# 3V-16V_to_5V3A_DC-DC_Converter.net
KiCad netlist of a schematic drawn in Altium Designer
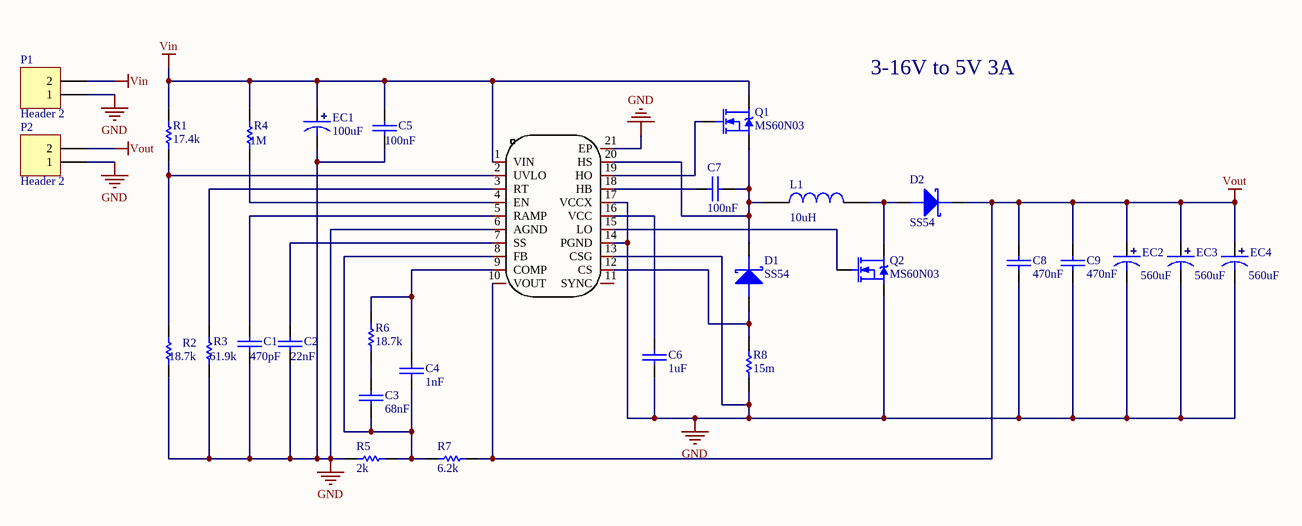
[diagram p0: 3V-16V to 5V3A DC-DC Converter.SchDoc]

(export (version "E")
  (design (tool "Eeschema 10.0.6"))
  (components
    (comp (ref "C1")
      (value "470pF")
      (footprint "0402C")
      (description "无极性电容")
      (libsource (lib "电容") (part "CAP"))
    )
    (comp (ref "C2")
      (value "22nF")
      (footprint "0402C")
      (description "无极性电容")
      (libsource (lib "电容") (part "CAP"))
    )
    (comp (ref "C3")
      (value "68nF")
      (footprint "0402C")
      (description "无极性电容")
      (libsource (lib "电容") (part "CAP"))
    )
    (comp (ref "C4")
      (value "1nF")
      (footprint "0402C")
      (description "无极性电容")
      (libsource (lib "电容") (part "CAP"))
    )
    (comp (ref "C5")
      (value "100nF")
      (footprint "0402C")
      (description "无极性电容")
      (libsource (lib "电容") (part "CAP"))
    )
    (comp (ref "C6")
      (value "1uF")
      (footprint "0402C")
      (description "无极性电容")
      (libsource (lib "电容") (part "CAP"))
    )
    (comp (ref "C7")
      (value "100nF")
      (footprint "0402C")
      (description "无极性电容")
      (libsource (lib "电容") (part "CAP"))
    )
    (comp (ref "C8")
      (value "470nF")
      (footprint "0402C")
      (description "无极性电容")
      (libsource (lib "电容") (part "CAP"))
    )
    (comp (ref "C9")
      (value "470nF")
      (footprint "0402C")
      (description "无极性电容")
      (libsource (lib "电容") (part "CAP"))
    )
    (comp (ref "D1")
      (value "SS54")
      (footprint "PCB库:肖特基二极管SS54")
      (description "肖特基二极管")
      (libsource (lib "二极管") (part "DIODE SCHOTTKY"))
    )
    (comp (ref "D2")
      (value "SS54")
      (footprint "PCB库:肖特基二极管SS54")
      (description "肖特基二极管")
      (libsource (lib "二极管") (part "DIODE SCHOTTKY"))
    )
    (comp (ref "EC1")
      (value "100uF")
      (footprint "SMD-EC6.3X6.3X10")
      (description "贴片电解电容")
      (libsource (lib "电容") (part "SMD_ECAP"))
    )
    (comp (ref "EC2")
      (value "560uF")
      (footprint "SMD-EC8X8X10")
      (description "贴片电解电容")
      (libsource (lib "电容") (part "SMD_ECAP"))
    )
    (comp (ref "EC3")
      (value "560uF")
      (footprint "SMD-EC8X8X10")
      (description "贴片电解电容")
      (libsource (lib "电容") (part "SMD_ECAP"))
    )
    (comp (ref "EC4")
      (value "560uF")
      (footprint "SMD-EC8X8X10")
      (description "贴片电解电容")
      (libsource (lib "电容") (part "SMD_ECAP"))
    )
    (comp (ref "L1")
      (value "10uH")
      (footprint "0630L")
      (description "INDUCTOR")
      (libsource (lib "电感") (part "INDUCTOR"))
    )
    (comp (ref "P1")
      (value "Header 2")
      (footprint "HDR1X2")
      (description "Header, 2-Pin")
      (fields (field (name "PUBLISHER") "Altium Limited"))
      (libsource (lib "Miscellaneous Connectors") (part "Header 2"))
    )
    (comp (ref "P2")
      (value "Header 2")
      (footprint "HDR1X2")
      (description "Header, 2-Pin")
      (fields (field (name "PUBLISHER") "Altium Limited"))
      (libsource (lib "Miscellaneous Connectors") (part "Header 2"))
    )
    (comp (ref "Q1")
      (value "MS60N03")
      (footprint "TO252")
      (description "N沟道场效应管")
      (libsource (lib "MOS管") (part "N-MOS"))
    )
    (comp (ref "Q2")
      (value "MS60N03")
      (footprint "TO252")
      (description "N沟道场效应管")
      (libsource (lib "MOS管") (part "N-MOS"))
    )
    (comp (ref "R1") (value "17.4k") (footprint "0402R") (libsource (lib "电阻") (part "RES")))
    (comp (ref "R2") (value "18.7k") (footprint "0402R") (libsource (lib "电阻") (part "RES")))
    (comp (ref "R3") (value "61.9k") (footprint "0402R") (libsource (lib "电阻") (part "RES")))
    (comp (ref "R4") (value "1M") (footprint "0402R") (libsource (lib "电阻") (part "RES")))
    (comp (ref "R5") (value "2k") (footprint "0402R") (libsource (lib "电阻") (part "RES")))
    (comp (ref "R6") (value "18.7k") (footprint "0402R") (libsource (lib "电阻") (part "RES")))
    (comp (ref "R7") (value "6.2k") (footprint "0402R") (libsource (lib "电阻") (part "RES")))
    (comp (ref "R8")
      (value "15m")
      (footprint "1206R")
      (description "P>0.2w")
      (libsource (lib "电阻") (part "RES"))
    )
    (comp (ref "U1")
      (value "LM25118MHX/NOPB")
      (footprint "PCB库:LM25118")
      (fields (field (name "MANUFACTURER") "TI(德州仪器)"))
      (libsource (lib "原理图库") (part "LM25118MHX/NOPB"))
    )
  )
  (nets
    (net (code "1") (name "GND") (class "Default")
      (node (ref "C1") (pin "1") (pinfunction "1_1") (pintype "passive"))
      (node (ref "C2") (pin "1") (pinfunction "1_1") (pintype "passive"))
      (node (ref "C5") (pin "1") (pinfunction "1_1") (pintype "passive"))
      (node (ref "C6") (pin "1") (pinfunction "1_1") (pintype "passive"))
      (node (ref "C8") (pin "2") (pinfunction "2_2") (pintype "passive"))
      (node (ref "C9") (pin "2") (pinfunction "2_2") (pintype "passive"))
      (node (ref "EC1") (pin "2") (pinfunction "2_2") (pintype "passive"))
      (node (ref "EC2") (pin "2") (pinfunction "2_2") (pintype "passive"))
      (node (ref "EC3") (pin "2") (pinfunction "2_2") (pintype "passive"))
      (node (ref "EC4") (pin "2") (pinfunction "2_2") (pintype "passive"))
      (node (ref "P1") (pin "1") (pinfunction "1_1") (pintype "passive"))
      (node (ref "P2") (pin "1") (pinfunction "1_1") (pintype "passive"))
      (node (ref "Q2") (pin "S") (pinfunction "S_S") (pintype "passive"))
      (node (ref "R2") (pin "1") (pinfunction "1_1") (pintype "passive"))
      (node (ref "R3") (pin "1") (pinfunction "1_1") (pintype "passive"))
      (node (ref "R5") (pin "1") (pinfunction "1_1") (pintype "passive"))
      (node (ref "R8") (pin "1") (pinfunction "1_1") (pintype "passive"))
      (node (ref "U1") (pin "13") (pinfunction "CSG_13") (pintype "passive"))
      (node (ref "U1") (pin "14") (pinfunction "PGND_14") (pintype "passive"))
      (node (ref "U1") (pin "17") (pinfunction "VCCX_17") (pintype "passive"))
      (node (ref "U1") (pin "21") (pinfunction "EP_21") (pintype "passive"))
      (node (ref "U1") (pin "6") (pinfunction "AGND_6") (pintype "passive"))
    )
    (net (code "2") (name "Net-(C3-Pad2)") (class "Default")
      (node (ref "C3") (pin "2") (pinfunction "2_2") (pintype "passive"))
      (node (ref "R6") (pin "1") (pinfunction "1_1") (pintype "passive"))
    )
    (net (code "3") (name "Net-(D2-Pad1)") (class "Default")
      (node (ref "D2") (pin "1") (pinfunction "1_1") (pintype "passive"))
      (node (ref "L1") (pin "2") (pinfunction "2_2") (pintype "passive"))
      (node (ref "Q2") (pin "D") (pinfunction "D_D") (pintype "passive"))
    )
    (net (code "4") (name "Net-(U1-COMP)") (class "Default")
      (node (ref "C4") (pin "2") (pinfunction "2_2") (pintype "passive"))
      (node (ref "R6") (pin "2") (pinfunction "2_2") (pintype "passive"))
      (node (ref "U1") (pin "9") (pinfunction "COMP_9") (pintype "passive"))
    )
    (net (code "5") (name "Net-(U1-CS)") (class "Default")
      (node (ref "D1") (pin "1") (pinfunction "1_1") (pintype "passive"))
      (node (ref "R8") (pin "2") (pinfunction "2_2") (pintype "passive"))
      (node (ref "U1") (pin "12") (pinfunction "CS_12") (pintype "passive"))
    )
    (net (code "6") (name "Net-(U1-EN)") (class "Default")
      (node (ref "R4") (pin "1") (pinfunction "1_1") (pintype "passive"))
      (node (ref "U1") (pin "4") (pinfunction "EN_4") (pintype "passive"))
    )
    (net (code "7") (name "Net-(U1-FB)") (class "Default")
      (node (ref "C3") (pin "1") (pinfunction "1_1") (pintype "passive"))
      (node (ref "C4") (pin "1") (pinfunction "1_1") (pintype "passive"))
      (node (ref "R5") (pin "2") (pinfunction "2_2") (pintype "passive"))
      (node (ref "R7") (pin "2") (pinfunction "2_2") (pintype "passive"))
      (node (ref "U1") (pin "8") (pinfunction "FB_8") (pintype "passive"))
    )
    (net (code "8") (name "Net-(U1-HB)") (class "Default")
      (node (ref "C7") (pin "2") (pinfunction "2_2") (pintype "passive"))
      (node (ref "U1") (pin "18") (pinfunction "HB_18") (pintype "passive"))
    )
    (net (code "9") (name "Net-(U1-HO)") (class "Default")
      (node (ref "Q1") (pin "G") (pinfunction "G_G") (pintype "passive"))
      (node (ref "U1") (pin "19") (pinfunction "HO_19") (pintype "passive"))
    )
    (net (code "10") (name "Net-(U1-HS)") (class "Default")
      (node (ref "C7") (pin "1") (pinfunction "1_1") (pintype "passive"))
      (node (ref "D1") (pin "2") (pinfunction "2_2") (pintype "passive"))
      (node (ref "L1") (pin "1") (pinfunction "1_1") (pintype "passive"))
      (node (ref "Q1") (pin "S") (pinfunction "S_S") (pintype "passive"))
      (node (ref "U1") (pin "20") (pinfunction "HS_20") (pintype "passive"))
    )
    (net (code "11") (name "Net-(U1-LO)") (class "Default")
      (node (ref "Q2") (pin "G") (pinfunction "G_G") (pintype "passive"))
      (node (ref "U1") (pin "15") (pinfunction "LO_15") (pintype "passive"))
    )
    (net (code "12") (name "Net-(U1-RAMP)") (class "Default")
      (node (ref "C1") (pin "2") (pinfunction "2_2") (pintype "passive"))
      (node (ref "U1") (pin "5") (pinfunction "RAMP_5") (pintype "passive"))
    )
    (net (code "13") (name "Net-(U1-RT)") (class "Default")
      (node (ref "R3") (pin "2") (pinfunction "2_2") (pintype "passive"))
      (node (ref "U1") (pin "3") (pinfunction "RT_3") (pintype "passive"))
    )
    (net (code "14") (name "Net-(U1-SS)") (class "Default")
      (node (ref "C2") (pin "2") (pinfunction "2_2") (pintype "passive"))
      (node (ref "U1") (pin "7") (pinfunction "SS_7") (pintype "passive"))
    )
    (net (code "15") (name "Net-(U1-UVLO)") (class "Default")
      (node (ref "R1") (pin "1") (pinfunction "1_1") (pintype "passive"))
      (node (ref "R2") (pin "2") (pinfunction "2_2") (pintype "passive"))
      (node (ref "U1") (pin "2") (pinfunction "UVLO_2") (pintype "passive"))
    )
    (net (code "16") (name "Net-(U1-VCC)") (class "Default")
      (node (ref "C6") (pin "2") (pinfunction "2_2") (pintype "passive"))
      (node (ref "U1") (pin "16") (pinfunction "VCC_16") (pintype "passive"))
    )
    (net (code "17") (name "Vin") (class "Default")
      (node (ref "C5") (pin "2") (pinfunction "2_2") (pintype "passive"))
      (node (ref "EC1") (pin "1") (pinfunction "1_1") (pintype "passive"))
      (node (ref "P1") (pin "2") (pinfunction "2_2") (pintype "passive"))
      (node (ref "Q1") (pin "D") (pinfunction "D_D") (pintype "passive"))
      (node (ref "R1") (pin "2") (pinfunction "2_2") (pintype "passive"))
      (node (ref "R4") (pin "2") (pinfunction "2_2") (pintype "passive"))
      (node (ref "U1") (pin "1") (pinfunction "VIN_1") (pintype "passive"))
    )
    (net (code "18") (name "Vout") (class "Default")
      (node (ref "C8") (pin "1") (pinfunction "1_1") (pintype "passive"))
      (node (ref "C9") (pin "1") (pinfunction "1_1") (pintype "passive"))
      (node (ref "D2") (pin "2") (pinfunction "2_2") (pintype "passive"))
      (node (ref "EC2") (pin "1") (pinfunction "1_1") (pintype "passive"))
      (node (ref "EC3") (pin "1") (pinfunction "1_1") (pintype "passive"))
      (node (ref "EC4") (pin "1") (pinfunction "1_1") (pintype "passive"))
      (node (ref "P2") (pin "2") (pinfunction "2_2") (pintype "passive"))
      (node (ref "R7") (pin "1") (pinfunction "1_1") (pintype "passive"))
      (node (ref "U1") (pin "10") (pinfunction "VOUT_10") (pintype "passive"))
    )
    (net (code "19") (name "unconnected-(U1-SYNC-Pad11)") (class "Default")
      (node (ref "U1") (pin "11") (pinfunction "SYNC_11") (pintype "passive"))
    )
  )
)
